# 7_seg_featherwing_rev_A.net
KiCad netlist of a schematic drawn in EAGLE
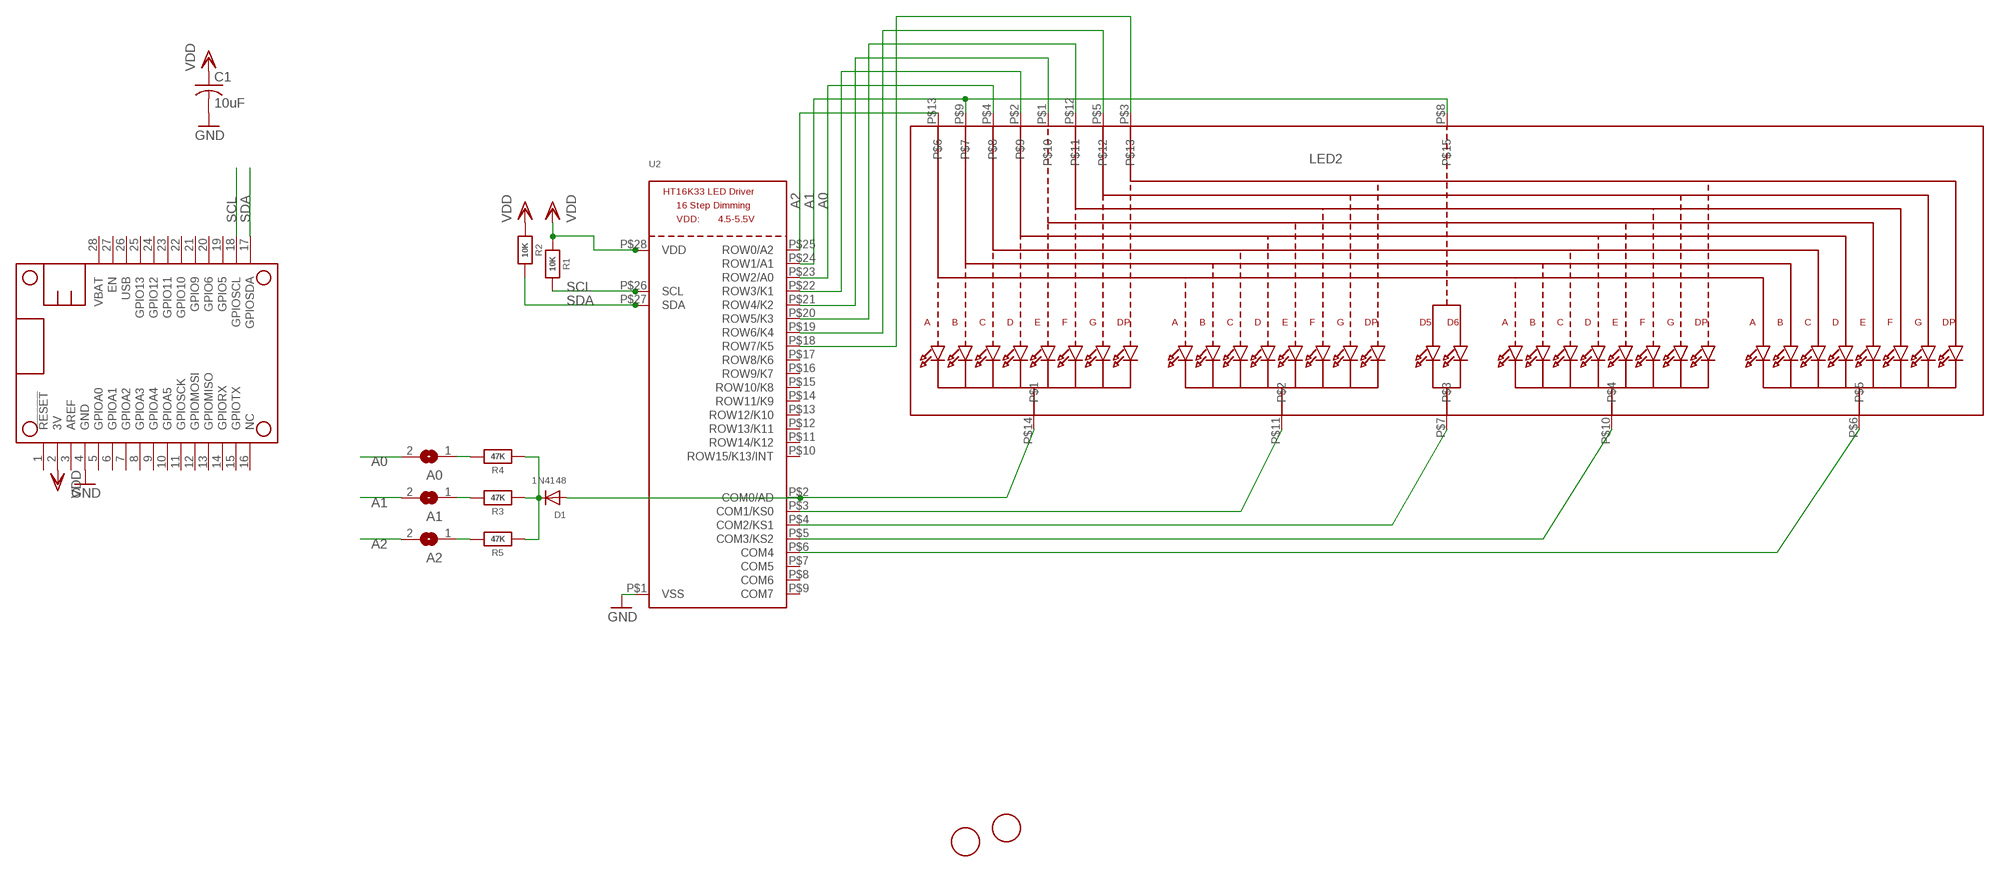
[diagram p0: schematic, sheet 1]

(export (version "E")
  (design (tool "Eeschema 10.0.6"))
  (components
    (comp (ref "A0")
      (value "SOLDERJUMPERREFLOW_NOPASTE")
      (footprint "eagle-import:SOLDERJUMPER_REFLOW_NOPASTE")
      (libsource (lib "eagle-import") (part "SOLDERJUMPERREFLOW_NOPASTE"))
    )
    (comp (ref "A1")
      (value "SOLDERJUMPERREFLOW_NOPASTE")
      (footprint "eagle-import:SOLDERJUMPER_REFLOW_NOPASTE")
      (libsource (lib "eagle-import") (part "SOLDERJUMPERREFLOW_NOPASTE"))
    )
    (comp (ref "A2")
      (value "SOLDERJUMPERREFLOW_NOPASTE")
      (footprint "eagle-import:SOLDERJUMPER_REFLOW_NOPASTE")
      (libsource (lib "eagle-import") (part "SOLDERJUMPERREFLOW_NOPASTE"))
    )
    (comp (ref "C1")
      (value "10uF")
      (footprint "eagle-import:C0805K")
      (libsource (lib "eagle-import") (part "C-USC0805K"))
    )
    (comp (ref "D1")
      (value "1N4148")
      (footprint "eagle-import:SOD-323F")
      (libsource (lib "eagle-import") (part "DIODESOD-323F"))
    )
    (comp (ref "LED2")
      (value "DISP_SEGMENT_4DIGIT_BL-Q56C43")
      (footprint "eagle-import:SEGMENT-BL-Q56C43")
      (libsource (lib "eagle-import") (part "DISP_SEGMENT_4DIGIT_BL-Q56C43"))
    )
    (comp (ref "MS1")
      (value "FEATHERWING")
      (footprint "eagle-import:FEATHERWING")
      (libsource (lib "eagle-import") (part "FEATHERWING"))
    )
    (comp (ref "R1")
      (value "10K")
      (footprint "eagle-import:0805-NO")
      (libsource (lib "eagle-import") (part "RESISTOR0805_NOOUTLINE"))
    )
    (comp (ref "R2")
      (value "10K")
      (footprint "eagle-import:0805-NO")
      (libsource (lib "eagle-import") (part "RESISTOR0805_NOOUTLINE"))
    )
    (comp (ref "R3")
      (value "47K")
      (footprint "eagle-import:0805-NO")
      (libsource (lib "eagle-import") (part "RESISTOR0805_NOOUTLINE"))
    )
    (comp (ref "R4")
      (value "47K")
      (footprint "eagle-import:0805-NO")
      (libsource (lib "eagle-import") (part "RESISTOR0805_NOOUTLINE"))
    )
    (comp (ref "R5")
      (value "47K")
      (footprint "eagle-import:0805-NO")
      (libsource (lib "eagle-import") (part "RESISTOR0805_NOOUTLINE"))
    )
    (comp (ref "U$1")
      (value "FIDUCIAL")
      (footprint "eagle-import:FIDUCIAL_1MM")
      (libsource (lib "eagle-import") (part "FIDUCIAL"))
    )
    (comp (ref "U$2")
      (value "FIDUCIAL")
      (footprint "eagle-import:FIDUCIAL_1MM")
      (libsource (lib "eagle-import") (part "FIDUCIAL"))
    )
    (comp (ref "U2")
      (value "HT16K33_SOP28_SKINNY")
      (footprint "eagle-import:SOP28_300MIL_SKINNY")
      (libsource (lib "eagle-import") (part "HT16K33_SOP28_SKINNY"))
    )
  )
  (nets
    (net (code "1") (name "/A0") (class "Default")
      (node (ref "A0") (pin "2") (pinfunction "2_2") (pintype "passive"))
      (node (ref "LED2") (pin "P$4") (pinfunction "P$8_P$4") (pintype "bidirectional"))
      (node (ref "U2") (pin "P$23") (pinfunction "ROW2/A0_P$23") (pintype "bidirectional"))
    )
    (net (code "2") (name "/A1") (class "Default")
      (node (ref "A1") (pin "2") (pinfunction "2_2") (pintype "passive"))
      (node (ref "LED2") (pin "P$8") (pinfunction "P$15_P$8") (pintype "bidirectional"))
      (node (ref "LED2") (pin "P$9") (pinfunction "P$7_P$9") (pintype "bidirectional"))
      (node (ref "U2") (pin "P$24") (pinfunction "ROW1/A1_P$24") (pintype "bidirectional"))
    )
    (net (code "3") (name "/A2") (class "Default")
      (node (ref "A2") (pin "2") (pinfunction "2_2") (pintype "passive"))
      (node (ref "LED2") (pin "P$13") (pinfunction "P$6_P$13") (pintype "bidirectional"))
      (node (ref "U2") (pin "P$25") (pinfunction "ROW0/A2_P$25") (pintype "bidirectional"))
    )
    (net (code "4") (name "/SCL") (class "Default")
      (node (ref "MS1") (pin "18") (pinfunction "GPIOSCL_18") (pintype "bidirectional"))
      (node (ref "R1") (pin "2") (pinfunction "2_2") (pintype "passive"))
      (node (ref "U2") (pin "P$26") (pinfunction "SCL_P$26") (pintype "bidirectional"))
    )
    (net (code "5") (name "/SDA") (class "Default")
      (node (ref "MS1") (pin "17") (pinfunction "GPIOSDA_17") (pintype "bidirectional"))
      (node (ref "R2") (pin "2") (pinfunction "2_2") (pintype "passive"))
      (node (ref "U2") (pin "P$27") (pinfunction "SDA_P$27") (pintype "bidirectional"))
    )
    (net (code "6") (name "/USB") (class "Default")
      (node (ref "MS1") (pin "26") (pinfunction "USB_26") (pintype "power_in"))
    )
    (net (code "7") (name "/VBAT") (class "Default")
      (node (ref "MS1") (pin "28") (pinfunction "VBAT_28") (pintype "power_in"))
    )
    (net (code "8") (name "GND") (class "Default")
      (node (ref "C1") (pin "2") (pinfunction "2_2") (pintype "passive"))
      (node (ref "MS1") (pin "4") (pinfunction "GND_4") (pintype "power_in"))
      (node (ref "U2") (pin "P$1") (pinfunction "VSS_P$1") (pintype "bidirectional"))
    )
    (net (code "9") (name "Net-(A0-Pad1)") (class "Default")
      (node (ref "A0") (pin "1") (pinfunction "1_1") (pintype "passive"))
      (node (ref "R4") (pin "2") (pinfunction "2_2") (pintype "passive"))
    )
    (net (code "10") (name "Net-(A1-Pad1)") (class "Default")
      (node (ref "A1") (pin "1") (pinfunction "1_1") (pintype "passive"))
      (node (ref "R3") (pin "2") (pinfunction "2_2") (pintype "passive"))
    )
    (net (code "11") (name "Net-(A2-Pad1)") (class "Default")
      (node (ref "A2") (pin "1") (pinfunction "1_1") (pintype "passive"))
      (node (ref "R5") (pin "2") (pinfunction "2_2") (pintype "passive"))
    )
    (net (code "12") (name "Net-(D1-PadC)") (class "Default")
      (node (ref "D1") (pin "C") (pinfunction "C_C") (pintype "passive"))
      (node (ref "R3") (pin "1") (pinfunction "1_1") (pintype "passive"))
      (node (ref "R4") (pin "1") (pinfunction "1_1") (pintype "passive"))
      (node (ref "R5") (pin "1") (pinfunction "1_1") (pintype "passive"))
    )
    (net (code "13") (name "Net-(LED2-P$1)") (class "Default")
      (node (ref "D1") (pin "A") (pinfunction "A_A") (pintype "passive"))
      (node (ref "LED2") (pin "P$14") (pinfunction "P$1_P$14") (pintype "bidirectional"))
      (node (ref "U2") (pin "P$2") (pinfunction "COM0/AD_P$2") (pintype "bidirectional"))
    )
    (net (code "14") (name "Net-(LED2-P$2)") (class "Default")
      (node (ref "LED2") (pin "P$11") (pinfunction "P$2_P$11") (pintype "bidirectional"))
      (node (ref "U2") (pin "P$3") (pinfunction "COM1/KS0_P$3") (pintype "bidirectional"))
    )
    (net (code "15") (name "Net-(LED2-P$3)") (class "Default")
      (node (ref "LED2") (pin "P$7") (pinfunction "P$3_P$7") (pintype "bidirectional"))
      (node (ref "U2") (pin "P$4") (pinfunction "COM2/KS1_P$4") (pintype "bidirectional"))
    )
    (net (code "16") (name "Net-(LED2-P$4)") (class "Default")
      (node (ref "LED2") (pin "P$10") (pinfunction "P$4_P$10") (pintype "bidirectional"))
      (node (ref "U2") (pin "P$5") (pinfunction "COM3/KS2_P$5") (pintype "bidirectional"))
    )
    (net (code "17") (name "Net-(LED2-P$5)") (class "Default")
      (node (ref "LED2") (pin "P$6") (pinfunction "P$5_P$6") (pintype "bidirectional"))
      (node (ref "U2") (pin "P$6") (pinfunction "COM4_P$6") (pintype "bidirectional"))
    )
    (net (code "18") (name "Net-(LED2-P$9)") (class "Default")
      (node (ref "LED2") (pin "P$2") (pinfunction "P$9_P$2") (pintype "bidirectional"))
      (node (ref "U2") (pin "P$22") (pinfunction "ROW3/K1_P$22") (pintype "bidirectional"))
    )
    (net (code "19") (name "Net-(LED2-P$10)") (class "Default")
      (node (ref "LED2") (pin "P$1") (pinfunction "P$10_P$1") (pintype "bidirectional"))
      (node (ref "U2") (pin "P$21") (pinfunction "ROW4/K2_P$21") (pintype "bidirectional"))
    )
    (net (code "20") (name "Net-(LED2-P$11)") (class "Default")
      (node (ref "LED2") (pin "P$12") (pinfunction "P$11_P$12") (pintype "bidirectional"))
      (node (ref "U2") (pin "P$20") (pinfunction "ROW5/K3_P$20") (pintype "bidirectional"))
    )
    (net (code "21") (name "Net-(LED2-P$12)") (class "Default")
      (node (ref "LED2") (pin "P$5") (pinfunction "P$12_P$5") (pintype "bidirectional"))
      (node (ref "U2") (pin "P$19") (pinfunction "ROW6/K4_P$19") (pintype "bidirectional"))
    )
    (net (code "22") (name "Net-(LED2-P$13)") (class "Default")
      (node (ref "LED2") (pin "P$3") (pinfunction "P$13_P$3") (pintype "bidirectional"))
      (node (ref "U2") (pin "P$18") (pinfunction "ROW7/K5_P$18") (pintype "bidirectional"))
    )
    (net (code "23") (name "VDD") (class "Default")
      (node (ref "C1") (pin "1") (pinfunction "1_1") (pintype "passive"))
      (node (ref "MS1") (pin "2") (pinfunction "3V_2") (pintype "power_in"))
      (node (ref "R1") (pin "1") (pinfunction "1_1") (pintype "passive"))
      (node (ref "R2") (pin "1") (pinfunction "1_1") (pintype "passive"))
      (node (ref "U2") (pin "P$28") (pinfunction "VDD_P$28") (pintype "bidirectional"))
    )
    (net (code "24") (name "unconnected-(MS1-AREF-Pad3)") (class "Default")
      (node (ref "MS1") (pin "3") (pinfunction "AREF_3") (pintype "passive"))
    )
    (net (code "25") (name "unconnected-(MS1-EN-Pad27)") (class "Default")
      (node (ref "MS1") (pin "27") (pinfunction "EN_27") (pintype "passive"))
    )
    (net (code "26") (name "unconnected-(MS1-GPIO5-Pad19)") (class "Default")
      (node (ref "MS1") (pin "19") (pinfunction "GPIO5_19") (pintype "bidirectional"))
    )
    (net (code "27") (name "unconnected-(MS1-GPIO6-Pad20)") (class "Default")
      (node (ref "MS1") (pin "20") (pinfunction "GPIO6_20") (pintype "bidirectional"))
    )
    (net (code "28") (name "unconnected-(MS1-GPIO9-Pad21)") (class "Default")
      (node (ref "MS1") (pin "21") (pinfunction "GPIO9_21") (pintype "bidirectional"))
    )
    (net (code "29") (name "unconnected-(MS1-GPIO10-Pad22)") (class "Default")
      (node (ref "MS1") (pin "22") (pinfunction "GPIO10_22") (pintype "bidirectional"))
    )
    (net (code "30") (name "unconnected-(MS1-GPIO11-Pad23)") (class "Default")
      (node (ref "MS1") (pin "23") (pinfunction "GPIO11_23") (pintype "bidirectional"))
    )
    (net (code "31") (name "unconnected-(MS1-GPIO12-Pad24)") (class "Default")
      (node (ref "MS1") (pin "24") (pinfunction "GPIO12_24") (pintype "bidirectional"))
    )
    (net (code "32") (name "unconnected-(MS1-GPIO13-Pad25)") (class "Default")
      (node (ref "MS1") (pin "25") (pinfunction "GPIO13_25") (pintype "bidirectional"))
    )
    (net (code "33") (name "unconnected-(MS1-GPIOA0-Pad5)") (class "Default")
      (node (ref "MS1") (pin "5") (pinfunction "GPIOA0_5") (pintype "bidirectional"))
    )
    (net (code "34") (name "unconnected-(MS1-GPIOA1-Pad6)") (class "Default")
      (node (ref "MS1") (pin "6") (pinfunction "GPIOA1_6") (pintype "bidirectional"))
    )
    (net (code "35") (name "unconnected-(MS1-GPIOA2-Pad7)") (class "Default")
      (node (ref "MS1") (pin "7") (pinfunction "GPIOA2_7") (pintype "bidirectional"))
    )
    (net (code "36") (name "unconnected-(MS1-GPIOA3-Pad8)") (class "Default")
      (node (ref "MS1") (pin "8") (pinfunction "GPIOA3_8") (pintype "bidirectional"))
    )
    (net (code "37") (name "unconnected-(MS1-GPIOA4-Pad9)") (class "Default")
      (node (ref "MS1") (pin "9") (pinfunction "GPIOA4_9") (pintype "bidirectional"))
    )
    (net (code "38") (name "unconnected-(MS1-GPIOA5-Pad10)") (class "Default")
      (node (ref "MS1") (pin "10") (pinfunction "GPIOA5_10") (pintype "bidirectional"))
    )
    (net (code "39") (name "unconnected-(MS1-GPIOMISO-Pad13)") (class "Default")
      (node (ref "MS1") (pin "13") (pinfunction "GPIOMISO_13") (pintype "bidirectional"))
    )
    (net (code "40") (name "unconnected-(MS1-GPIOMOSI-Pad12)") (class "Default")
      (node (ref "MS1") (pin "12") (pinfunction "GPIOMOSI_12") (pintype "bidirectional"))
    )
    (net (code "41") (name "unconnected-(MS1-GPIORX-Pad14)") (class "Default")
      (node (ref "MS1") (pin "14") (pinfunction "GPIORX_14") (pintype "bidirectional"))
    )
    (net (code "42") (name "unconnected-(MS1-GPIOSCK-Pad11)") (class "Default")
      (node (ref "MS1") (pin "11") (pinfunction "GPIOSCK_11") (pintype "bidirectional"))
    )
    (net (code "43") (name "unconnected-(MS1-GPIOTX-Pad15)") (class "Default")
      (node (ref "MS1") (pin "15") (pinfunction "GPIOTX_15") (pintype "bidirectional"))
    )
    (net (code "44") (name "unconnected-(MS1-NC-Pad16)") (class "Default")
      (node (ref "MS1") (pin "16") (pinfunction "NC_16") (pintype "passive"))
    )
    (net (code "45") (name "unconnected-(MS1-~{RESET}-Pad1)") (class "Default")
      (node (ref "MS1") (pin "1") (pinfunction "~{RESET}_1") (pintype "input"))
    )
    (net (code "46") (name "unconnected-(U2-COM5-PadP$7)") (class "Default")
      (node (ref "U2") (pin "P$7") (pinfunction "COM5_P$7") (pintype "bidirectional"))
    )
    (net (code "47") (name "unconnected-(U2-COM6-PadP$8)") (class "Default")
      (node (ref "U2") (pin "P$8") (pinfunction "COM6_P$8") (pintype "bidirectional"))
    )
    (net (code "48") (name "unconnected-(U2-COM7-PadP$9)") (class "Default")
      (node (ref "U2") (pin "P$9") (pinfunction "COM7_P$9") (pintype "bidirectional"))
    )
    (net (code "49") (name "unconnected-(U2-ROW8{slash}K6-PadP$17)") (class "Default")
      (node (ref "U2") (pin "P$17") (pinfunction "ROW8/K6_P$17") (pintype "bidirectional"))
    )
    (net (code "50") (name "unconnected-(U2-ROW9{slash}K7-PadP$16)") (class "Default")
      (node (ref "U2") (pin "P$16") (pinfunction "ROW9/K7_P$16") (pintype "bidirectional"))
    )
    (net (code "51") (name "unconnected-(U2-ROW10{slash}K8-PadP$15)") (class "Default")
      (node (ref "U2") (pin "P$15") (pinfunction "ROW10/K8_P$15") (pintype "bidirectional"))
    )
    (net (code "52") (name "unconnected-(U2-ROW11{slash}K9-PadP$14)") (class "Default")
      (node (ref "U2") (pin "P$14") (pinfunction "ROW11/K9_P$14") (pintype "bidirectional"))
    )
    (net (code "53") (name "unconnected-(U2-ROW12{slash}K10-PadP$13)") (class "Default")
      (node (ref "U2") (pin "P$13") (pinfunction "ROW12/K10_P$13") (pintype "bidirectional"))
    )
    (net (code "54") (name "unconnected-(U2-ROW13{slash}K11-PadP$12)") (class "Default")
      (node (ref "U2") (pin "P$12") (pinfunction "ROW13/K11_P$12") (pintype "bidirectional"))
    )
    (net (code "55") (name "unconnected-(U2-ROW14{slash}K12-PadP$11)") (class "Default")
      (node (ref "U2") (pin "P$11") (pinfunction "ROW14/K12_P$11") (pintype "bidirectional"))
    )
    (net (code "56") (name "unconnected-(U2-ROW15{slash}K13{slash}INT-PadP$10)") (class "Default")
      (node (ref "U2") (pin "P$10") (pinfunction "ROW15/K13/INT_P$10") (pintype "bidirectional"))
    )
  )
)
